# AMU-S06-V00-IsolatedCAN4.net
KiCad netlist of a schematic drawn in Altium Designer
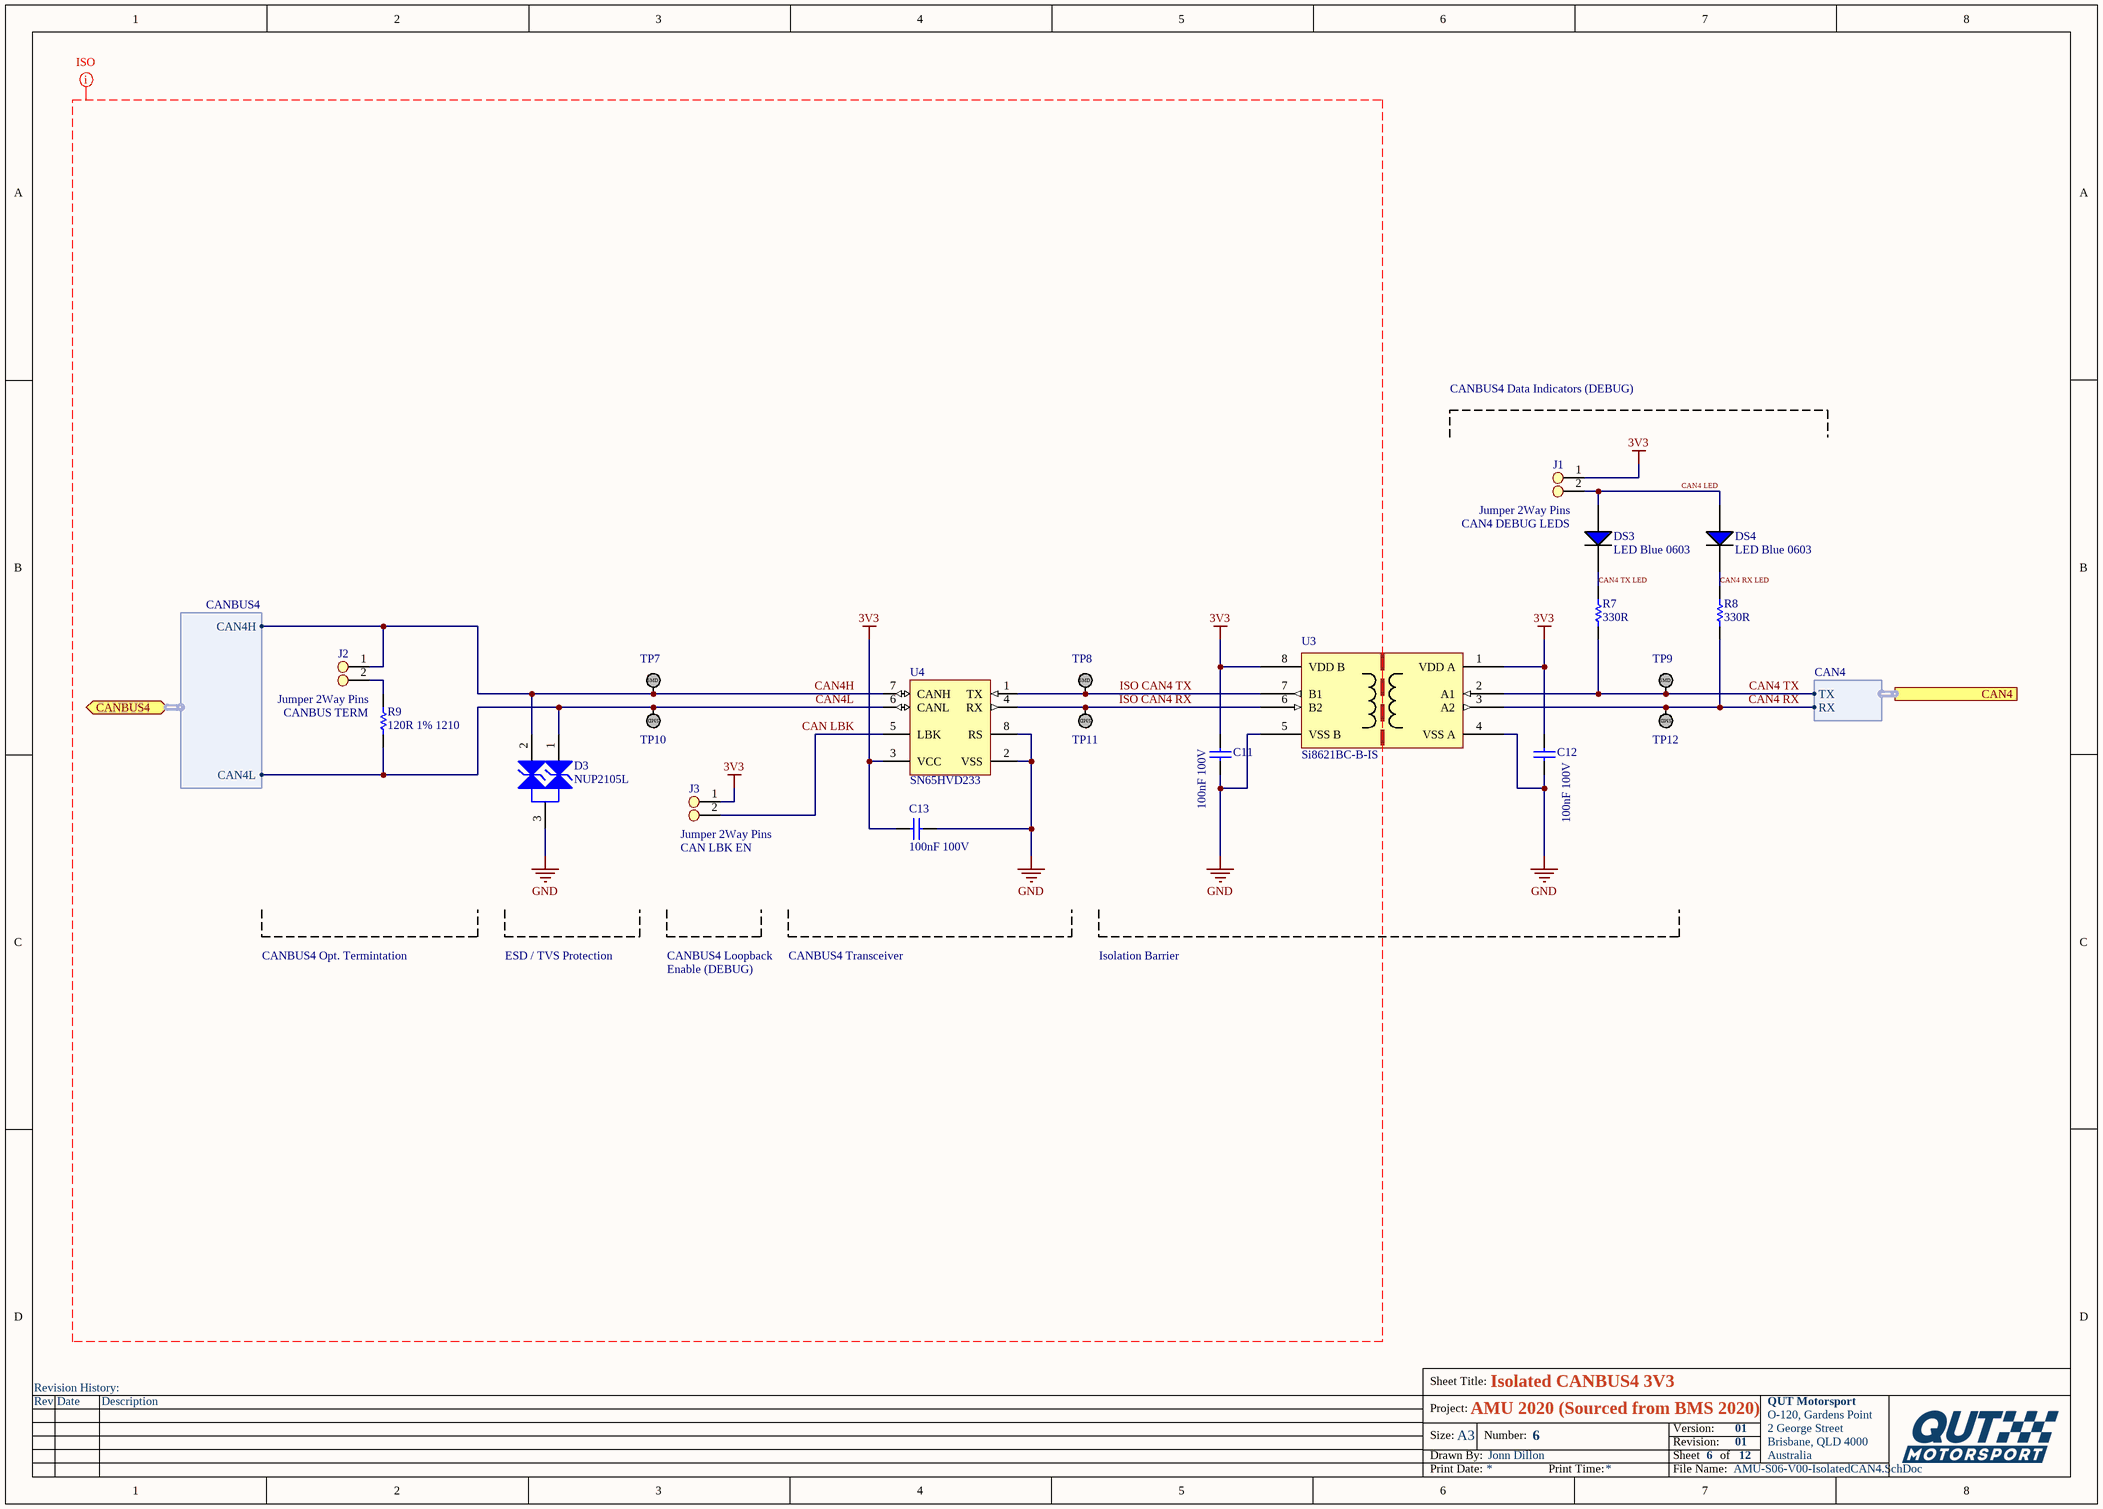
[diagram p0: AMU-S06-V00-IsolatedCAN4.SchDoc]

(export (version "E")
  (design (tool "Eeschema 10.0.6"))
  (components
    (comp (ref "C11")
      (value "100nF 100V")
      (footprint "Cap_Ceramic_0603")
      (description "Capacitor, Ceramic, SMD, 100nF, 100V, 5%, X7R, 0603")
      (libsource (lib "StandardCapacitors") (part "100nF 100V 5% X7R 0603"))
    )
    (comp (ref "C12")
      (value "100nF 100V")
      (footprint "Cap_Ceramic_0603")
      (description "Capacitor, Ceramic, SMD, 100nF, 100V, 5%, X7R, 0603")
      (libsource (lib "StandardCapacitors") (part "100nF 100V 5% X7R 0603"))
    )
    (comp (ref "C13")
      (value "100nF 100V")
      (footprint "Cap_Ceramic_0603")
      (description "Capacitor, Ceramic, SMD, 100nF, 100V, 5%, X7R, 0603")
      (libsource (lib "StandardCapacitors") (part "100nF 100V 5% X7R 0603"))
    )
    (comp (ref "D3")
      (value "NUP2105L")
      (footprint "NUP2105L")
      (libsource (lib "QUTMS_CANLibrary") (part "NUP2105L"))
    )
    (comp (ref "DS3")
      (value "LED Blue 0603")
      (footprint "LED BLUE 0603")
      (libsource (lib "QUTMS_LEDLibrary") (part "LED BLUE 0603"))
    )
    (comp (ref "DS4")
      (value "LED Blue 0603")
      (footprint "LED BLUE 0603")
      (libsource (lib "QUTMS_LEDLibrary") (part "LED BLUE 0603"))
    )
    (comp (ref "J1")
      (value "Jumper 2Way Pins")
      (footprint "Jumper_2Way_Pin")
      (description "Jumper 2Way Side Pins")
      (libsource (lib "QUTMS_JumperLibrary") (part "Jumper 2Way Side Pins"))
    )
    (comp (ref "J2")
      (value "Jumper 2Way Pins")
      (footprint "Jumper_2Way_Pin")
      (description "Jumper 2Way Side Pins")
      (libsource (lib "QUTMS_JumperLibrary") (part "Jumper 2Way Side Pins"))
    )
    (comp (ref "J3")
      (value "Jumper 2Way Pins")
      (footprint "Jumper_2Way_Pin")
      (description "Jumper 2Way Side Pins")
      (libsource (lib "QUTMS_JumperLibrary") (part "Jumper 2Way Side Pins"))
    )
    (comp (ref "R7")
      (value "330R")
      (footprint "Res_ThinFilm_0603")
      (description "Resistor, SMD, 330R, 0.1W, 5%, 0603")
      (libsource (lib "StandardResistors") (part "330R 5% 0603"))
    )
    (comp (ref "R8")
      (value "330R")
      (footprint "Res_ThinFilm_0603")
      (description "Resistor, SMD, 330R, 0.1W, 5%, 0603")
      (libsource (lib "StandardResistors") (part "330R 5% 0603"))
    )
    (comp (ref "R9")
      (value "120R 1% 1210")
      (footprint "Res_ThinFilm_1210")
      (description "Resistor, SMD, 120R, 0.25W, 1%, 1210")
      (libsource (lib "StandardResistors") (part "120R 1% 1210"))
    )
    (comp (ref "TP7")
      (value "TestPoint_SMD")
      (footprint "TestPointSMD")
      (libsource (lib "StandardTest") (part "TestPoint_SMD"))
    )
    (comp (ref "TP8")
      (value "TestPoint_SMD")
      (footprint "TestPointSMD")
      (libsource (lib "StandardTest") (part "TestPoint_SMD"))
    )
    (comp (ref "TP9")
      (value "TestPoint_SMD")
      (footprint "TestPointSMD")
      (libsource (lib "StandardTest") (part "TestPoint_SMD"))
    )
    (comp (ref "TP10")
      (value "TestPoint_SMD")
      (footprint "TestPointSMD")
      (libsource (lib "StandardTest") (part "TestPoint_SMD"))
    )
    (comp (ref "TP11")
      (value "TestPoint_SMD")
      (footprint "TestPointSMD")
      (libsource (lib "StandardTest") (part "TestPoint_SMD"))
    )
    (comp (ref "TP12")
      (value "TestPoint_SMD")
      (footprint "TestPointSMD")
      (libsource (lib "StandardTest") (part "TestPoint_SMD"))
    )
    (comp (ref "U3")
      (value "Si8621BC-B-IS")
      (footprint "Si8621BC-B-IS")
      (libsource (lib "QUTMS_IsolatorLibrary") (part "Si8621BC-B-IS"))
    )
    (comp (ref "U4")
      (value "SN65HVD233")
      (footprint "SN65HVD233DR")
      (libsource (lib "QUTMS_CANLibrary") (part "SN65HVD233"))
    )
  )
  (nets
    (net (code "3") (name "/CAN LBK") (class "Default")
      (node (ref "J3") (pin "2") (pinfunction "2_2") (pintype "passive"))
      (node (ref "U4") (pin "5") (pinfunction "LBK_5") (pintype "passive"))
    )
    (net (code "4") (name "/CAN4 LED") (class "Default")
      (node (ref "DS3") (pin "1") (pinfunction "A_1") (pintype "passive"))
      (node (ref "DS4") (pin "1") (pinfunction "A_1") (pintype "passive"))
      (node (ref "J1") (pin "2") (pinfunction "2_2") (pintype "passive"))
    )
    (net (code "5") (name "/CAN4 RX") (class "Default")
      (node (ref "R8") (pin "1") (pinfunction "1_1") (pintype "passive"))
      (node (ref "TP12") (pin "1") (pinfunction "1_1") (pintype "passive"))
      (node (ref "U3") (pin "3") (pinfunction "A2_3") (pintype "output"))
    )
    (net (code "6") (name "/CAN4 RX LED") (class "Default")
      (node (ref "DS4") (pin "2") (pinfunction "C_2") (pintype "passive"))
      (node (ref "R8") (pin "2") (pinfunction "2_2") (pintype "passive"))
    )
    (net (code "7") (name "/CAN4 TX") (class "Default")
      (node (ref "R7") (pin "1") (pinfunction "1_1") (pintype "passive"))
      (node (ref "TP9") (pin "1") (pinfunction "1_1") (pintype "passive"))
      (node (ref "U3") (pin "2") (pinfunction "A1_2") (pintype "input"))
    )
    (net (code "8") (name "/CAN4 TX LED") (class "Default")
      (node (ref "DS3") (pin "2") (pinfunction "C_2") (pintype "passive"))
      (node (ref "R7") (pin "2") (pinfunction "2_2") (pintype "passive"))
    )
    (net (code "9") (name "/CAN4H") (class "Default")
      (node (ref "D3") (pin "2") (pinfunction "2_2") (pintype "passive"))
      (node (ref "J2") (pin "1") (pinfunction "1_1") (pintype "passive"))
      (node (ref "TP7") (pin "1") (pinfunction "1_1") (pintype "passive"))
      (node (ref "U4") (pin "7") (pinfunction "CANH_7") (pintype "bidirectional"))
    )
    (net (code "10") (name "/CAN4L") (class "Default")
      (node (ref "D3") (pin "1") (pinfunction "1_1") (pintype "passive"))
      (node (ref "R9") (pin "1") (pinfunction "1_1") (pintype "passive"))
      (node (ref "TP10") (pin "1") (pinfunction "1_1") (pintype "passive"))
      (node (ref "U4") (pin "6") (pinfunction "CANL_6") (pintype "bidirectional"))
    )
    (net (code "11") (name "/ISO CAN4 RX") (class "Default")
      (node (ref "TP11") (pin "1") (pinfunction "1_1") (pintype "passive"))
      (node (ref "U3") (pin "6") (pinfunction "B2_6") (pintype "input"))
      (node (ref "U4") (pin "4") (pinfunction "RX_4") (pintype "output"))
    )
    (net (code "12") (name "/ISO CAN4 TX") (class "Default")
      (node (ref "TP8") (pin "1") (pinfunction "1_1") (pintype "passive"))
      (node (ref "U3") (pin "7") (pinfunction "B1_7") (pintype "output"))
      (node (ref "U4") (pin "1") (pinfunction "TX_1") (pintype "input"))
    )
    (net (code "15") (name "3V3") (class "Default")
      (node (ref "C11") (pin "2") (pinfunction "2_2") (pintype "passive"))
      (node (ref "C12") (pin "2") (pinfunction "2_2") (pintype "passive"))
      (node (ref "C13") (pin "2") (pinfunction "2_2") (pintype "passive"))
      (node (ref "J1") (pin "1") (pinfunction "1_1") (pintype "passive"))
      (node (ref "J3") (pin "1") (pinfunction "1_1") (pintype "passive"))
      (node (ref "U3") (pin "1") (pinfunction "VDD_A_1") (pintype "passive"))
      (node (ref "U3") (pin "8") (pinfunction "VDD_B_8") (pintype "passive"))
      (node (ref "U4") (pin "3") (pinfunction "VCC_3") (pintype "passive"))
    )
    (net (code "16") (name "GND") (class "Default")
      (node (ref "C11") (pin "1") (pinfunction "1_1") (pintype "passive"))
      (node (ref "C12") (pin "1") (pinfunction "1_1") (pintype "passive"))
      (node (ref "C13") (pin "1") (pinfunction "1_1") (pintype "passive"))
      (node (ref "D3") (pin "3") (pinfunction "3_3") (pintype "passive"))
      (node (ref "U3") (pin "4") (pinfunction "VSS_A_4") (pintype "passive"))
      (node (ref "U3") (pin "5") (pinfunction "VSS_B_5") (pintype "passive"))
      (node (ref "U4") (pin "2") (pinfunction "VSS_2") (pintype "passive"))
      (node (ref "U4") (pin "8") (pinfunction "RS_8") (pintype "passive"))
    )
    (net (code "17") (name "Net-(J2-Pad2)") (class "Default")
      (node (ref "J2") (pin "2") (pinfunction "2_2") (pintype "passive"))
      (node (ref "R9") (pin "2") (pinfunction "2_2") (pintype "passive"))
    )
  )
)
